# HSYNC_100px.net
KiCad netlist of a schematic drawn in EAGLE
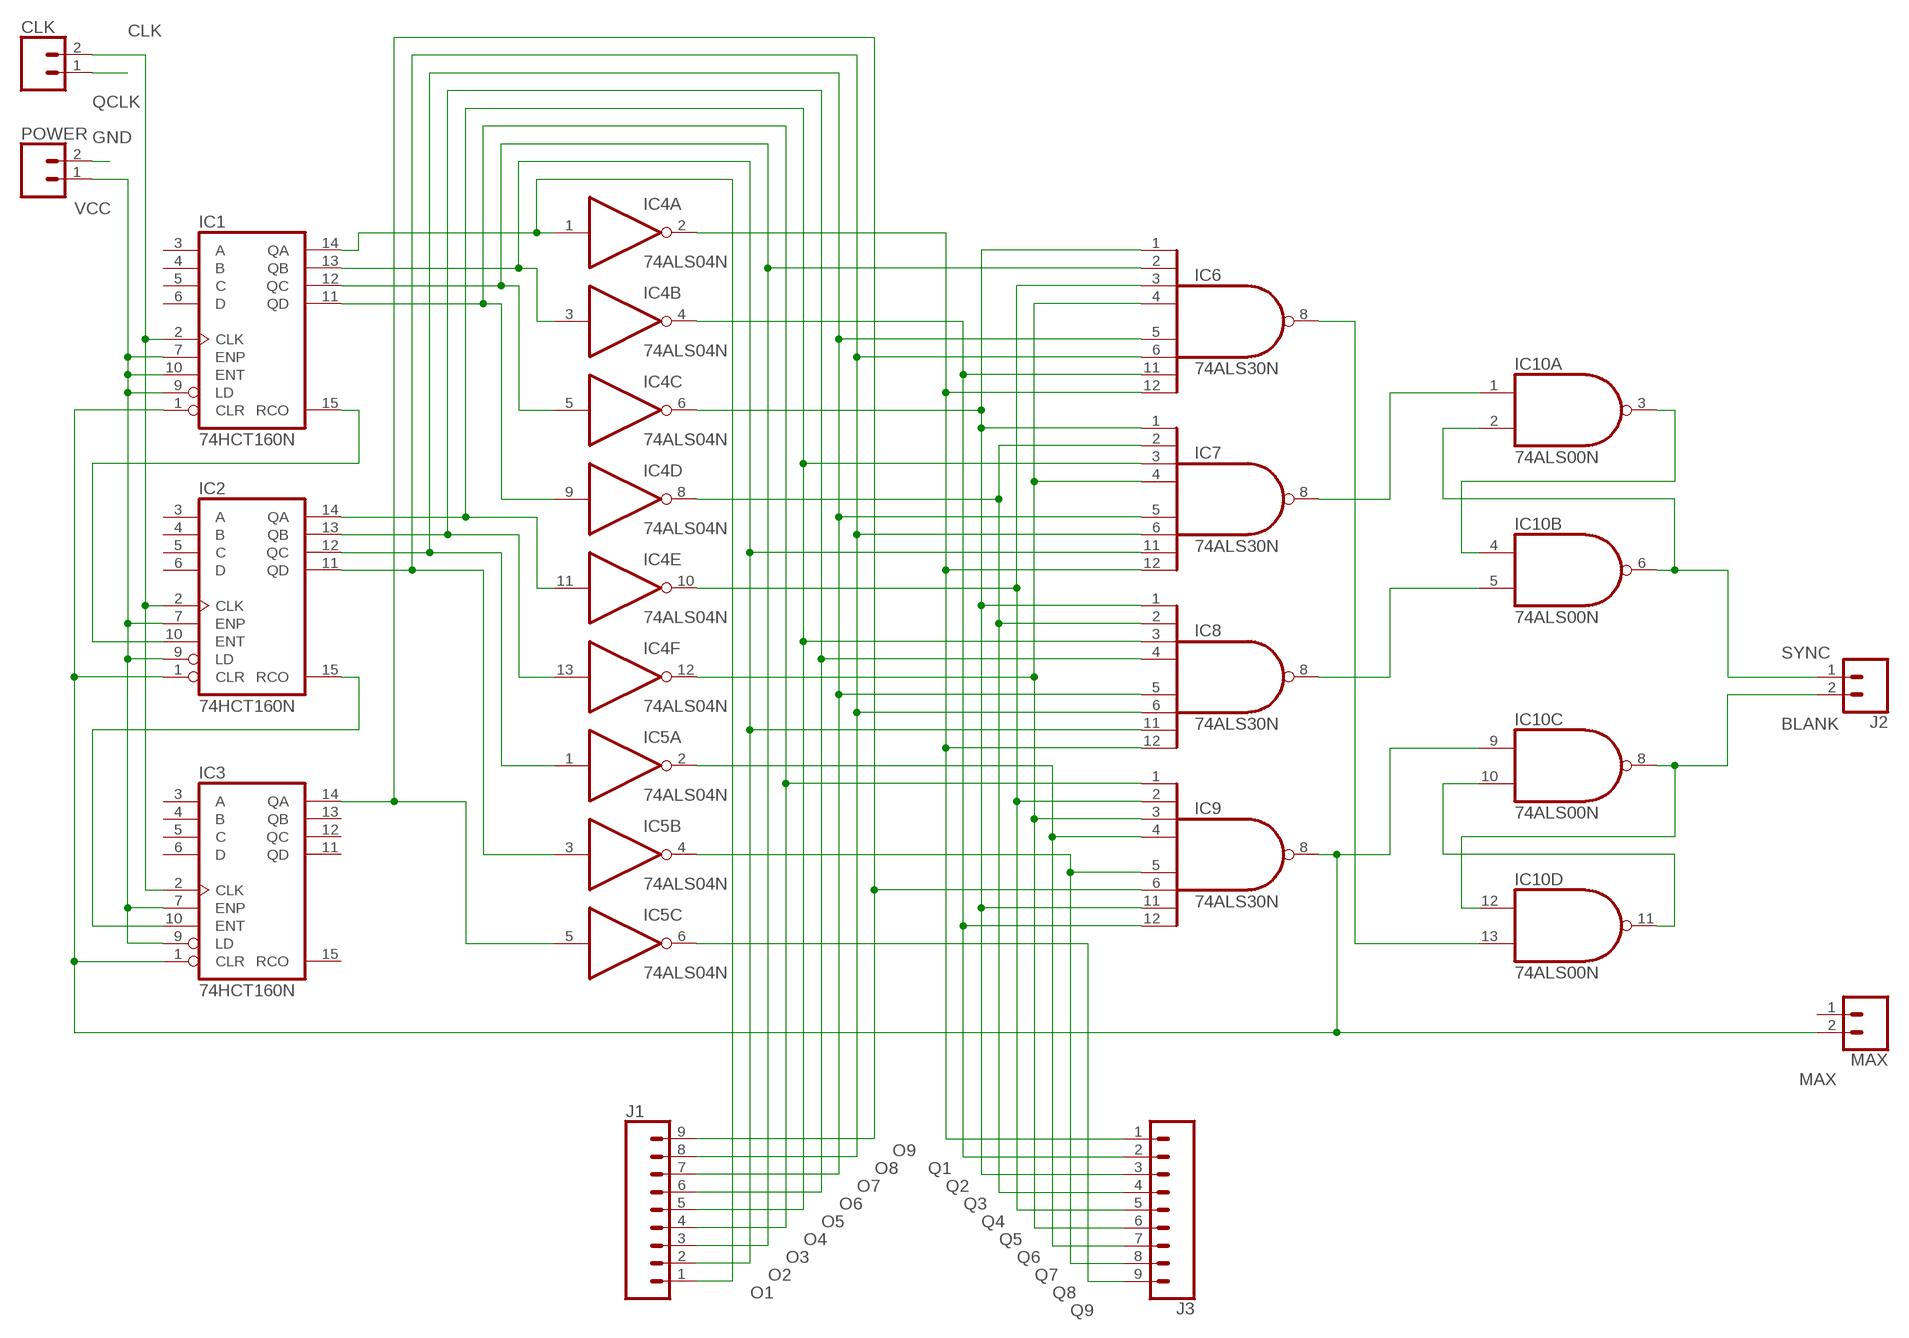
[diagram p0: schematic, sheet 1]

(export (version "E")
  (design (tool "Eeschema 10.0.6"))
  (components
    (comp (ref "CLK")
      (value "CONN_02POGO_PIN_HOLES_ONLY")
      (footprint "eagle-import:1X02_PP_HOLES_ONLY")
      (libsource (lib "eagle-import") (part "CONN_02POGO_PIN_HOLES_ONLY"))
    )
    (comp (ref "IC1")
      (value "74HCT160N")
      (footprint "eagle-import:DIL16")
      (libsource (lib "eagle-import") (part "74160NHCT"))
    )
    (comp (ref "IC2")
      (value "74HCT160N")
      (footprint "eagle-import:DIL16")
      (libsource (lib "eagle-import") (part "74160NHCT"))
    )
    (comp (ref "IC3")
      (value "74HCT160N")
      (footprint "eagle-import:DIL16")
      (libsource (lib "eagle-import") (part "74160NHCT"))
    )
    (comp (ref "IC4")
      (value "74ALS04N")
      (footprint "eagle-import:DIL14")
      (libsource (lib "eagle-import") (part "7404NALS"))
    )
    (comp (ref "IC5")
      (value "74ALS04N")
      (footprint "eagle-import:DIL14")
      (libsource (lib "eagle-import") (part "7404NALS"))
    )
    (comp (ref "IC6")
      (value "74ALS30N")
      (footprint "eagle-import:DIL14")
      (libsource (lib "eagle-import") (part "7430NALS"))
    )
    (comp (ref "IC7")
      (value "74ALS30N")
      (footprint "eagle-import:DIL14")
      (libsource (lib "eagle-import") (part "7430NALS"))
    )
    (comp (ref "IC8")
      (value "74ALS30N")
      (footprint "eagle-import:DIL14")
      (libsource (lib "eagle-import") (part "7430NALS"))
    )
    (comp (ref "IC9")
      (value "74ALS30N")
      (footprint "eagle-import:DIL14")
      (libsource (lib "eagle-import") (part "7430NALS"))
    )
    (comp (ref "IC10")
      (value "74ALS00N")
      (footprint "eagle-import:DIL14")
      (libsource (lib "eagle-import") (part "7400NALS"))
    )
    (comp (ref "J1")
      (value "CONN_09")
      (footprint "eagle-import:1X09")
      (libsource (lib "eagle-import") (part "CONN_09"))
    )
    (comp (ref "J2")
      (value "CONN_02POGO_PIN_HOLES_ONLY")
      (footprint "eagle-import:1X02_PP_HOLES_ONLY")
      (libsource (lib "eagle-import") (part "CONN_02POGO_PIN_HOLES_ONLY"))
    )
    (comp (ref "J3")
      (value "CONN_09")
      (footprint "eagle-import:1X09")
      (libsource (lib "eagle-import") (part "CONN_09"))
    )
    (comp (ref "MAX")
      (value "CONN_02POGO_PIN_HOLES_ONLY")
      (footprint "eagle-import:1X02_PP_HOLES_ONLY")
      (libsource (lib "eagle-import") (part "CONN_02POGO_PIN_HOLES_ONLY"))
    )
    (comp (ref "POWER")
      (value "CONN_02POGO_PIN_HOLES_ONLY")
      (footprint "eagle-import:1X02_PP_HOLES_ONLY")
      (libsource (lib "eagle-import") (part "CONN_02POGO_PIN_HOLES_ONLY"))
    )
  )
  (nets
    (net (code "1") (name "/BLANK") (class "Default")
      (node (ref "IC10") (pin "12") (pinfunction "I0_12") (pintype "input"))
      (node (ref "IC10") (pin "8") (pinfunction "O_8") (pintype "output"))
      (node (ref "J2") (pin "2") (pinfunction "2_2") (pintype "passive"))
    )
    (net (code "2") (name "/CLK") (class "Default")
      (node (ref "CLK") (pin "2") (pinfunction "2_2") (pintype "passive"))
      (node (ref "IC1") (pin "2") (pinfunction "CLK_2") (pintype "input"))
      (node (ref "IC2") (pin "2") (pinfunction "CLK_2") (pintype "input"))
      (node (ref "IC3") (pin "2") (pinfunction "CLK_2") (pintype "input"))
    )
    (net (code "3") (name "/GND") (class "Default")
      (node (ref "POWER") (pin "2") (pinfunction "2_2") (pintype "passive"))
    )
    (net (code "4") (name "/MAX") (class "Default")
      (node (ref "IC1") (pin "1") (pinfunction "CLR_1") (pintype "input"))
      (node (ref "IC10") (pin "9") (pinfunction "I0_9") (pintype "input"))
      (node (ref "IC2") (pin "1") (pinfunction "CLR_1") (pintype "input"))
      (node (ref "IC3") (pin "1") (pinfunction "CLR_1") (pintype "input"))
      (node (ref "IC9") (pin "8") (pinfunction "O_8") (pintype "output"))
      (node (ref "MAX") (pin "2") (pinfunction "2_2") (pintype "passive"))
    )
    (net (code "5") (name "/O1") (class "Default")
      (node (ref "IC1") (pin "14") (pinfunction "QA_14") (pintype "output"))
      (node (ref "IC4") (pin "1") (pinfunction "I_1") (pintype "input"))
      (node (ref "J1") (pin "1") (pinfunction "1_1") (pintype "passive"))
    )
    (net (code "6") (name "/O2") (class "Default")
      (node (ref "IC1") (pin "13") (pinfunction "QB_13") (pintype "output"))
      (node (ref "IC4") (pin "3") (pinfunction "I_3") (pintype "input"))
      (node (ref "IC7") (pin "11") (pinfunction "I6_11") (pintype "input"))
      (node (ref "IC8") (pin "11") (pinfunction "I6_11") (pintype "input"))
      (node (ref "J1") (pin "2") (pinfunction "2_2") (pintype "passive"))
    )
    (net (code "7") (name "/O3") (class "Default")
      (node (ref "IC1") (pin "12") (pinfunction "QC_12") (pintype "output"))
      (node (ref "IC4") (pin "5") (pinfunction "I_5") (pintype "input"))
      (node (ref "IC6") (pin "2") (pinfunction "I1_2") (pintype "input"))
      (node (ref "J1") (pin "3") (pinfunction "3_3") (pintype "passive"))
    )
    (net (code "8") (name "/O4") (class "Default")
      (node (ref "IC1") (pin "11") (pinfunction "QD_11") (pintype "output"))
      (node (ref "IC4") (pin "9") (pinfunction "I_9") (pintype "input"))
      (node (ref "IC9") (pin "1") (pinfunction "I0_1") (pintype "input"))
      (node (ref "J1") (pin "4") (pinfunction "4_4") (pintype "passive"))
    )
    (net (code "9") (name "/O5") (class "Default")
      (node (ref "IC2") (pin "14") (pinfunction "QA_14") (pintype "output"))
      (node (ref "IC4") (pin "11") (pinfunction "I_11") (pintype "input"))
      (node (ref "IC7") (pin "3") (pinfunction "I2_3") (pintype "input"))
      (node (ref "IC8") (pin "3") (pinfunction "I2_3") (pintype "input"))
      (node (ref "J1") (pin "5") (pinfunction "5_5") (pintype "passive"))
    )
    (net (code "10") (name "/O6") (class "Default")
      (node (ref "IC2") (pin "13") (pinfunction "QB_13") (pintype "output"))
      (node (ref "IC4") (pin "13") (pinfunction "I_13") (pintype "input"))
      (node (ref "IC8") (pin "4") (pinfunction "I3_4") (pintype "input"))
      (node (ref "J1") (pin "6") (pinfunction "6_6") (pintype "passive"))
    )
    (net (code "11") (name "/O7") (class "Default")
      (node (ref "IC2") (pin "12") (pinfunction "QC_12") (pintype "output"))
      (node (ref "IC5") (pin "1") (pinfunction "I_1") (pintype "input"))
      (node (ref "IC6") (pin "5") (pinfunction "I4_5") (pintype "input"))
      (node (ref "IC7") (pin "5") (pinfunction "I4_5") (pintype "input"))
      (node (ref "IC8") (pin "5") (pinfunction "I4_5") (pintype "input"))
      (node (ref "J1") (pin "7") (pinfunction "7_7") (pintype "passive"))
    )
    (net (code "12") (name "/O8") (class "Default")
      (node (ref "IC2") (pin "11") (pinfunction "QD_11") (pintype "output"))
      (node (ref "IC5") (pin "3") (pinfunction "I_3") (pintype "input"))
      (node (ref "IC6") (pin "6") (pinfunction "I5_6") (pintype "input"))
      (node (ref "IC7") (pin "6") (pinfunction "I5_6") (pintype "input"))
      (node (ref "IC8") (pin "6") (pinfunction "I5_6") (pintype "input"))
      (node (ref "J1") (pin "8") (pinfunction "8_8") (pintype "passive"))
    )
    (net (code "13") (name "/O9") (class "Default")
      (node (ref "IC3") (pin "14") (pinfunction "QA_14") (pintype "output"))
      (node (ref "IC5") (pin "5") (pinfunction "I_5") (pintype "input"))
      (node (ref "IC9") (pin "6") (pinfunction "I5_6") (pintype "input"))
      (node (ref "J1") (pin "9") (pinfunction "9_9") (pintype "passive"))
    )
    (net (code "14") (name "/Q1") (class "Default")
      (node (ref "IC4") (pin "2") (pinfunction "O_2") (pintype "output"))
      (node (ref "IC6") (pin "12") (pinfunction "I7_12") (pintype "input"))
      (node (ref "IC7") (pin "12") (pinfunction "I7_12") (pintype "input"))
      (node (ref "IC8") (pin "12") (pinfunction "I7_12") (pintype "input"))
      (node (ref "J3") (pin "1") (pinfunction "1_1") (pintype "passive"))
    )
    (net (code "15") (name "/Q2") (class "Default")
      (node (ref "IC4") (pin "4") (pinfunction "O_4") (pintype "output"))
      (node (ref "IC6") (pin "11") (pinfunction "I6_11") (pintype "input"))
      (node (ref "IC9") (pin "12") (pinfunction "I7_12") (pintype "input"))
      (node (ref "J3") (pin "2") (pinfunction "2_2") (pintype "passive"))
    )
    (net (code "16") (name "/Q3") (class "Default")
      (node (ref "IC4") (pin "6") (pinfunction "O_6") (pintype "output"))
      (node (ref "IC6") (pin "1") (pinfunction "I0_1") (pintype "input"))
      (node (ref "IC7") (pin "1") (pinfunction "I0_1") (pintype "input"))
      (node (ref "IC8") (pin "1") (pinfunction "I0_1") (pintype "input"))
      (node (ref "IC9") (pin "11") (pinfunction "I6_11") (pintype "input"))
      (node (ref "J3") (pin "3") (pinfunction "3_3") (pintype "passive"))
    )
    (net (code "17") (name "/Q4") (class "Default")
      (node (ref "IC4") (pin "8") (pinfunction "O_8") (pintype "output"))
      (node (ref "IC7") (pin "2") (pinfunction "I1_2") (pintype "input"))
      (node (ref "IC8") (pin "2") (pinfunction "I1_2") (pintype "input"))
      (node (ref "J3") (pin "4") (pinfunction "4_4") (pintype "passive"))
    )
    (net (code "18") (name "/Q5") (class "Default")
      (node (ref "IC4") (pin "10") (pinfunction "O_10") (pintype "output"))
      (node (ref "IC6") (pin "3") (pinfunction "I2_3") (pintype "input"))
      (node (ref "IC9") (pin "2") (pinfunction "I1_2") (pintype "input"))
      (node (ref "J3") (pin "5") (pinfunction "5_5") (pintype "passive"))
    )
    (net (code "19") (name "/Q6") (class "Default")
      (node (ref "IC4") (pin "12") (pinfunction "O_12") (pintype "output"))
      (node (ref "IC6") (pin "4") (pinfunction "I3_4") (pintype "input"))
      (node (ref "IC7") (pin "4") (pinfunction "I3_4") (pintype "input"))
      (node (ref "IC9") (pin "3") (pinfunction "I2_3") (pintype "input"))
      (node (ref "J3") (pin "6") (pinfunction "6_6") (pintype "passive"))
    )
    (net (code "20") (name "/Q7") (class "Default")
      (node (ref "IC5") (pin "2") (pinfunction "O_2") (pintype "output"))
      (node (ref "IC9") (pin "4") (pinfunction "I3_4") (pintype "input"))
      (node (ref "J3") (pin "7") (pinfunction "7_7") (pintype "passive"))
    )
    (net (code "21") (name "/Q8") (class "Default")
      (node (ref "IC5") (pin "4") (pinfunction "O_4") (pintype "output"))
      (node (ref "IC9") (pin "5") (pinfunction "I4_5") (pintype "input"))
      (node (ref "J3") (pin "8") (pinfunction "8_8") (pintype "passive"))
    )
    (net (code "22") (name "/Q9") (class "Default")
      (node (ref "IC5") (pin "6") (pinfunction "O_6") (pintype "output"))
      (node (ref "J3") (pin "9") (pinfunction "9_9") (pintype "passive"))
    )
    (net (code "23") (name "/QCLK") (class "Default")
      (node (ref "CLK") (pin "1") (pinfunction "1_1") (pintype "passive"))
    )
    (net (code "24") (name "/SYNC") (class "Default")
      (node (ref "IC10") (pin "2") (pinfunction "I1_2") (pintype "input"))
      (node (ref "IC10") (pin "6") (pinfunction "O_6") (pintype "output"))
      (node (ref "J2") (pin "1") (pinfunction "1_1") (pintype "passive"))
    )
    (net (code "25") (name "/VCC") (class "Default")
      (node (ref "IC1") (pin "10") (pinfunction "ENT_10") (pintype "input"))
      (node (ref "IC1") (pin "7") (pinfunction "ENP_7") (pintype "input"))
      (node (ref "IC1") (pin "9") (pinfunction "LD_9") (pintype "input"))
      (node (ref "IC2") (pin "7") (pinfunction "ENP_7") (pintype "input"))
      (node (ref "IC2") (pin "9") (pinfunction "LD_9") (pintype "input"))
      (node (ref "IC3") (pin "7") (pinfunction "ENP_7") (pintype "input"))
      (node (ref "IC3") (pin "9") (pinfunction "LD_9") (pintype "input"))
      (node (ref "POWER") (pin "1") (pinfunction "1_1") (pintype "passive"))
    )
    (net (code "26") (name "Net-(IC1A-RCO)") (class "Default")
      (node (ref "IC1") (pin "15") (pinfunction "RCO_15") (pintype "output"))
      (node (ref "IC2") (pin "10") (pinfunction "ENT_10") (pintype "input"))
    )
    (net (code "27") (name "Net-(IC2A-RCO)") (class "Default")
      (node (ref "IC2") (pin "15") (pinfunction "RCO_15") (pintype "output"))
      (node (ref "IC3") (pin "10") (pinfunction "ENT_10") (pintype "input"))
    )
    (net (code "28") (name "Net-(IC10A-I0)") (class "Default")
      (node (ref "IC10") (pin "1") (pinfunction "I0_1") (pintype "input"))
      (node (ref "IC7") (pin "8") (pinfunction "O_8") (pintype "output"))
    )
    (net (code "29") (name "Net-(IC10A-O)") (class "Default")
      (node (ref "IC10") (pin "3") (pinfunction "O_3") (pintype "output"))
      (node (ref "IC10") (pin "4") (pinfunction "I0_4") (pintype "input"))
    )
    (net (code "30") (name "Net-(IC10B-I1)") (class "Default")
      (node (ref "IC10") (pin "5") (pinfunction "I1_5") (pintype "input"))
      (node (ref "IC8") (pin "8") (pinfunction "O_8") (pintype "output"))
    )
    (net (code "31") (name "Net-(IC10C-I1)") (class "Default")
      (node (ref "IC10") (pin "10") (pinfunction "I1_10") (pintype "input"))
      (node (ref "IC10") (pin "11") (pinfunction "O_11") (pintype "output"))
    )
    (net (code "32") (name "Net-(IC10D-I1)") (class "Default")
      (node (ref "IC10") (pin "13") (pinfunction "I1_13") (pintype "input"))
      (node (ref "IC6") (pin "8") (pinfunction "O_8") (pintype "output"))
    )
    (net (code "33") (name "unconnected-(IC1A-A-Pad3)") (class "Default")
      (node (ref "IC1") (pin "3") (pinfunction "A_3") (pintype "input"))
    )
    (net (code "34") (name "unconnected-(IC1A-B-Pad4)") (class "Default")
      (node (ref "IC1") (pin "4") (pinfunction "B_4") (pintype "input"))
    )
    (net (code "35") (name "unconnected-(IC1A-C-Pad5)") (class "Default")
      (node (ref "IC1") (pin "5") (pinfunction "C_5") (pintype "input"))
    )
    (net (code "36") (name "unconnected-(IC1A-D-Pad6)") (class "Default")
      (node (ref "IC1") (pin "6") (pinfunction "D_6") (pintype "input"))
    )
    (net (code "37") (name "unconnected-(IC2A-A-Pad3)") (class "Default")
      (node (ref "IC2") (pin "3") (pinfunction "A_3") (pintype "input"))
    )
    (net (code "38") (name "unconnected-(IC2A-B-Pad4)") (class "Default")
      (node (ref "IC2") (pin "4") (pinfunction "B_4") (pintype "input"))
    )
    (net (code "39") (name "unconnected-(IC2A-C-Pad5)") (class "Default")
      (node (ref "IC2") (pin "5") (pinfunction "C_5") (pintype "input"))
    )
    (net (code "40") (name "unconnected-(IC2A-D-Pad6)") (class "Default")
      (node (ref "IC2") (pin "6") (pinfunction "D_6") (pintype "input"))
    )
    (net (code "41") (name "unconnected-(IC3A-A-Pad3)") (class "Default")
      (node (ref "IC3") (pin "3") (pinfunction "A_3") (pintype "input"))
    )
    (net (code "42") (name "unconnected-(IC3A-B-Pad4)") (class "Default")
      (node (ref "IC3") (pin "4") (pinfunction "B_4") (pintype "input"))
    )
    (net (code "43") (name "unconnected-(IC3A-C-Pad5)") (class "Default")
      (node (ref "IC3") (pin "5") (pinfunction "C_5") (pintype "input"))
    )
    (net (code "44") (name "unconnected-(IC3A-D-Pad6)") (class "Default")
      (node (ref "IC3") (pin "6") (pinfunction "D_6") (pintype "input"))
    )
    (net (code "45") (name "unconnected-(IC3A-QB-Pad13)") (class "Default")
      (node (ref "IC3") (pin "13") (pinfunction "QB_13") (pintype "output"))
    )
    (net (code "46") (name "unconnected-(IC3A-QC-Pad12)") (class "Default")
      (node (ref "IC3") (pin "12") (pinfunction "QC_12") (pintype "output"))
    )
    (net (code "47") (name "unconnected-(IC3A-QD-Pad11)") (class "Default")
      (node (ref "IC3") (pin "11") (pinfunction "QD_11") (pintype "output"))
    )
    (net (code "48") (name "unconnected-(IC3A-RCO-Pad15)") (class "Default")
      (node (ref "IC3") (pin "15") (pinfunction "RCO_15") (pintype "output"))
    )
    (net (code "49") (name "unconnected-(MAX-Pad1)") (class "Default")
      (node (ref "MAX") (pin "1") (pinfunction "1_1") (pintype "passive"))
    )
  )
)
